# Voice.net
KiCad netlist of a schematic drawn in Altium Designer
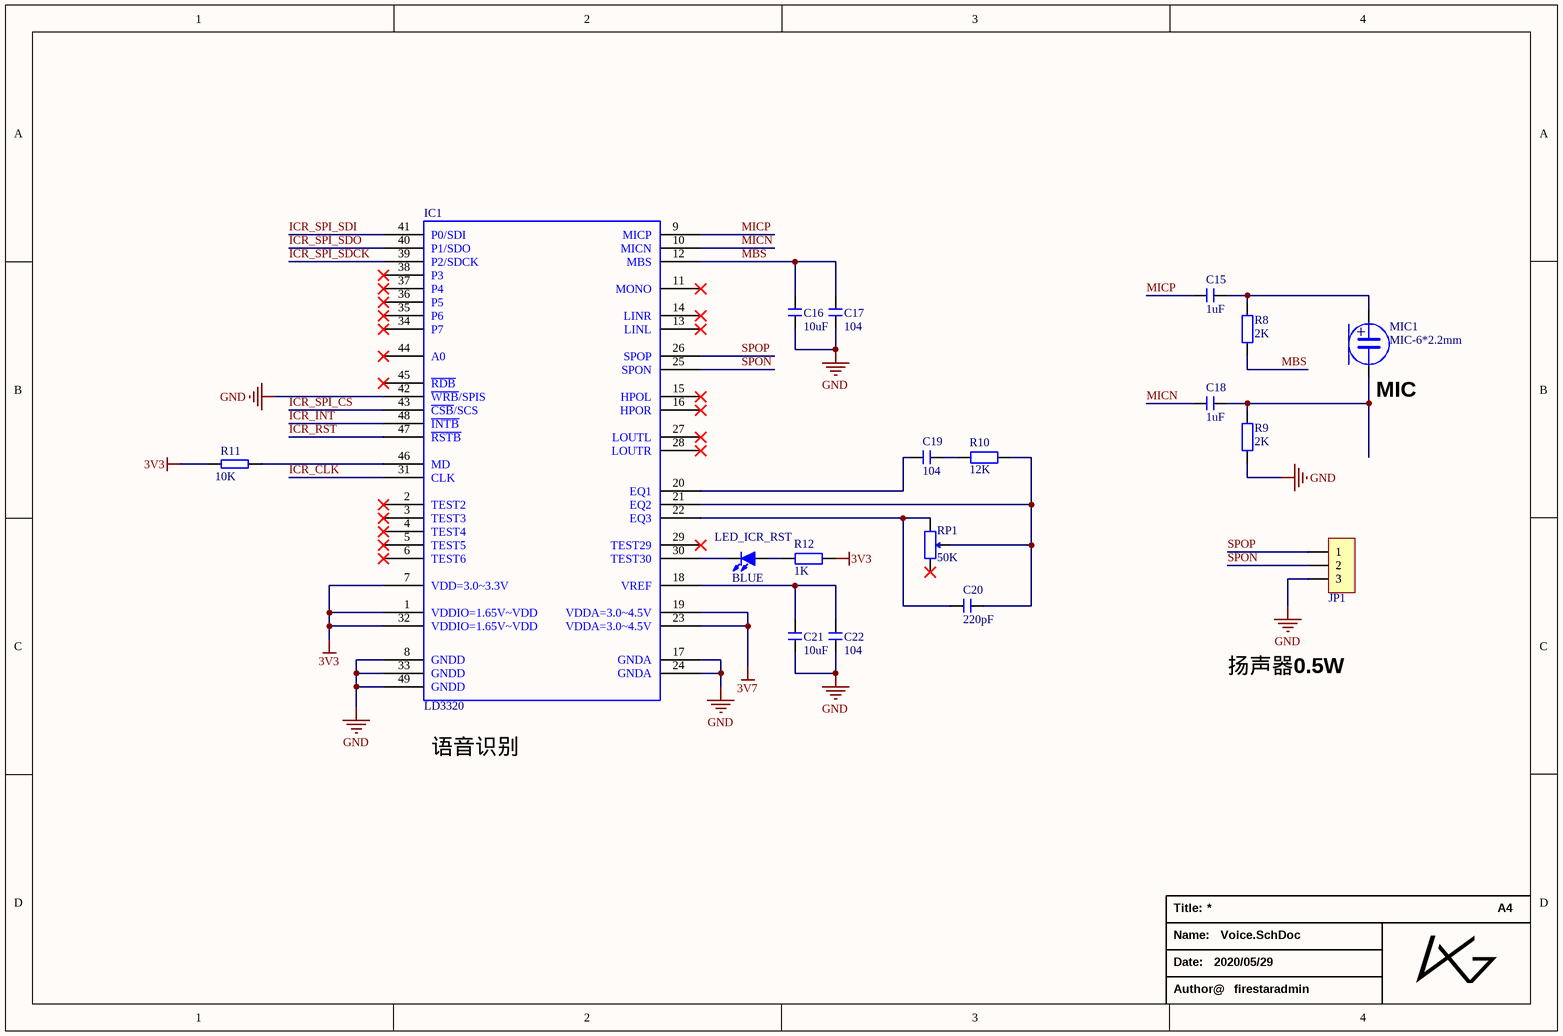
[diagram p0: Voice.SchDoc]

(export (version "E")
  (design (tool "Eeschema 10.0.6"))
  (components
    (comp (ref "C15")
      (value "1uF")
      (footprint "C 0603_M")
      (description "无极性贴片电容")
      (fields (field (name "版权归属") "源创客"))
      (libsource (lib "3.1   - 电阻-电容-电感") (part "C"))
    )
    (comp (ref "C16")
      (value "10uF")
      (footprint "C 0805_M")
      (description "无极性贴片电容")
      (fields (field (name "版权归属") "源创客"))
      (libsource (lib "3.1   - 电阻-电容-电感") (part "C"))
    )
    (comp (ref "C17")
      (value "104")
      (footprint "C 0603_M")
      (description "无极性贴片电容")
      (fields (field (name "版权归属") "源创客"))
      (libsource (lib "3.1   - 电阻-电容-电感") (part "C"))
    )
    (comp (ref "C18")
      (value "1uF")
      (footprint "C 0603_M")
      (description "无极性贴片电容")
      (fields (field (name "版权归属") "源创客"))
      (libsource (lib "3.1   - 电阻-电容-电感") (part "C"))
    )
    (comp (ref "C19")
      (value "104")
      (footprint "C 0603_M")
      (description "无极性贴片电容")
      (fields (field (name "版权归属") "源创客"))
      (libsource (lib "3.1   - 电阻-电容-电感") (part "C"))
    )
    (comp (ref "C20")
      (value "220pF")
      (footprint "C 0603_M")
      (description "无极性贴片电容")
      (fields (field (name "版权归属") "源创客"))
      (libsource (lib "3.1   - 电阻-电容-电感") (part "C"))
    )
    (comp (ref "C21")
      (value "10uF")
      (footprint "C 0805_M")
      (description "无极性贴片电容")
      (fields (field (name "版权归属") "源创客"))
      (libsource (lib "3.1   - 电阻-电容-电感") (part "C"))
    )
    (comp (ref "C22")
      (value "104")
      (footprint "C 0603_M")
      (description "无极性贴片电容")
      (fields (field (name "版权归属") "源创客"))
      (libsource (lib "3.1   - 电阻-电容-电感") (part "C"))
    )
    (comp (ref "IC1")
      (value "LD3320")
      (footprint "QFN48 7X7_M")
      (libsource (lib "1.1   - IC芯片") (part "LD3320"))
    )
    (comp (ref "JP1")
      (value "HDR-1X3")
      (footprint "HDR2.54-LI-3P")
      (description "3P接插件")
      (fields (field (name "版权归属") "源创客"))
      (libsource (lib "4.5   - 接插件-脚距2.54") (part "Header 3"))
    )
    (comp (ref "LED_ICR_RST")
      (value "BLUE")
      (footprint "LED 0603B")
      (description "贴片LED")
      (fields (field (name "版权归属") "源创客"))
      (libsource (lib "9.1   - LED") (part "LED-SMD"))
    )
    (comp (ref "MIC1")
      (value "MIC-6*2.2mm")
      (footprint "MIC-6*2.2MM")
      (description "电容麦克风")
      (fields (field (name "版权归属") "源创客"))
      (libsource (lib "11.1 - 传感元件") (part "MIC1"))
    )
    (comp (ref "R8")
      (value "2K")
      (footprint "R 0805_M")
      (description "贴片电阻")
      (fields (field (name "版权归属") "源创客"))
      (libsource (lib "3.1   - 电阻-电容-电感") (part "R"))
    )
    (comp (ref "R9")
      (value "2K")
      (footprint "R 0805_M")
      (description "贴片电阻")
      (fields (field (name "版权归属") "源创客"))
      (libsource (lib "3.1   - 电阻-电容-电感") (part "R"))
    )
    (comp (ref "R10")
      (value "12K")
      (footprint "R 0805_M")
      (description "贴片电阻")
      (fields (field (name "版权归属") "源创客"))
      (libsource (lib "3.1   - 电阻-电容-电感") (part "R"))
    )
    (comp (ref "R11") (value "10K") (footprint "R 0603_M") (libsource (lib "ZIBO V2.0_Main") (part "R")))
    (comp (ref "R12")
      (value "1K")
      (footprint "R 0805_M")
      (description "贴片电阻")
      (fields (field (name "版权归属") "源创客"))
      (libsource (lib "3.1   - 电阻-电容-电感") (part "R"))
    )
    (comp (ref "RP1")
      (value "50K")
      (footprint "3306W")
      (description "插件单联电位器")
      (fields (field (name "版权归属") "源创客"))
      (libsource (lib "3.1   - 电阻-电容-电感") (part "RP-ID"))
    )
  )
  (nets
    (net (code "1") (name "/ICR_CLK") (class "Default")
      (node (ref "IC1") (pin "31") (pinfunction "CLK_31") (pintype "passive"))
    )
    (net (code "2") (name "/ICR_INT") (class "Default")
      (node (ref "IC1") (pin "48") (pinfunction "~{INTB}_48") (pintype "passive"))
    )
    (net (code "3") (name "/ICR_RST") (class "Default")
      (node (ref "IC1") (pin "47") (pinfunction "~{RSTB}_47") (pintype "passive"))
    )
    (net (code "4") (name "/ICR_SPI_CS") (class "Default")
      (node (ref "IC1") (pin "43") (pinfunction "~{CSB}/SCS_43") (pintype "passive"))
    )
    (net (code "5") (name "/ICR_SPI_SDCK") (class "Default")
      (node (ref "IC1") (pin "39") (pinfunction "P2/SDCK_39") (pintype "passive"))
    )
    (net (code "6") (name "/ICR_SPI_SDI") (class "Default")
      (node (ref "IC1") (pin "41") (pinfunction "P0/SDI_41") (pintype "passive"))
    )
    (net (code "7") (name "/ICR_SPI_SDO") (class "Default")
      (node (ref "IC1") (pin "40") (pinfunction "P1/SDO_40") (pintype "passive"))
    )
    (net (code "8") (name "/MBS") (class "Default")
      (node (ref "C16") (pin "2") (pinfunction "2_2") (pintype "passive"))
      (node (ref "C17") (pin "2") (pinfunction "2_2") (pintype "passive"))
      (node (ref "IC1") (pin "12") (pinfunction "MBS_12") (pintype "passive"))
      (node (ref "R8") (pin "1") (pinfunction "1_1") (pintype "passive"))
    )
    (net (code "9") (name "/MICN") (class "Default")
      (node (ref "C18") (pin "2") (pinfunction "2_2") (pintype "passive"))
      (node (ref "IC1") (pin "10") (pinfunction "MICN_10") (pintype "passive"))
    )
    (net (code "10") (name "/MICP") (class "Default")
      (node (ref "C15") (pin "2") (pinfunction "2_2") (pintype "passive"))
      (node (ref "IC1") (pin "9") (pinfunction "MICP_9") (pintype "passive"))
    )
    (net (code "11") (name "/SPON") (class "Default")
      (node (ref "IC1") (pin "25") (pinfunction "SPON_25") (pintype "passive"))
      (node (ref "JP1") (pin "2") (pinfunction "2_2") (pintype "passive"))
    )
    (net (code "12") (name "/SPOP") (class "Default")
      (node (ref "IC1") (pin "26") (pinfunction "SPOP_26") (pintype "passive"))
      (node (ref "JP1") (pin "1") (pinfunction "1_1") (pintype "passive"))
    )
    (net (code "13") (name "3V3") (class "Default")
      (node (ref "IC1") (pin "1") (pinfunction "VDDIO=1.65V~VDD_1") (pintype "passive"))
      (node (ref "IC1") (pin "32") (pinfunction "VDDIO=1.65V~VDD_32") (pintype "passive"))
      (node (ref "IC1") (pin "7") (pinfunction "VDD=3.0~3.3V_7") (pintype "passive"))
      (node (ref "R11") (pin "1") (pinfunction "1_1") (pintype "passive"))
      (node (ref "R12") (pin "2") (pinfunction "2_2") (pintype "passive"))
    )
    (net (code "14") (name "3V7") (class "Default")
      (node (ref "IC1") (pin "19") (pinfunction "VDDA=3.0~4.5V_19") (pintype "passive"))
      (node (ref "IC1") (pin "23") (pinfunction "VDDA=3.0~4.5V_23") (pintype "passive"))
    )
    (net (code "15") (name "GND") (class "Default")
      (node (ref "C16") (pin "1") (pinfunction "1_1") (pintype "passive"))
      (node (ref "C17") (pin "1") (pinfunction "1_1") (pintype "passive"))
      (node (ref "C21") (pin "1") (pinfunction "1_1") (pintype "passive"))
      (node (ref "C22") (pin "1") (pinfunction "1_1") (pintype "passive"))
      (node (ref "IC1") (pin "17") (pinfunction "GNDA_17") (pintype "passive"))
      (node (ref "IC1") (pin "24") (pinfunction "GNDA_24") (pintype "passive"))
      (node (ref "IC1") (pin "33") (pinfunction "GNDD_33") (pintype "passive"))
      (node (ref "IC1") (pin "42") (pinfunction "~{WRB}/SPIS_42") (pintype "passive"))
      (node (ref "IC1") (pin "49") (pinfunction "GNDD_49") (pintype "passive"))
      (node (ref "IC1") (pin "8") (pinfunction "GNDD_8") (pintype "passive"))
      (node (ref "JP1") (pin "3") (pinfunction "3_3") (pintype "passive"))
      (node (ref "R9") (pin "1") (pinfunction "1_1") (pintype "passive"))
    )
    (net (code "16") (name "Net-(C15-Pad1)") (class "Default")
      (node (ref "C15") (pin "1") (pinfunction "1_1") (pintype "passive"))
      (node (ref "MIC1") (pin "1") (pinfunction "1_1") (pintype "passive"))
      (node (ref "R8") (pin "2") (pinfunction "2_2") (pintype "passive"))
    )
    (net (code "17") (name "Net-(C18-Pad1)") (class "Default")
      (node (ref "C18") (pin "1") (pinfunction "1_1") (pintype "passive"))
      (node (ref "MIC1") (pin "2") (pinfunction "2_2") (pintype "passive"))
      (node (ref "R9") (pin "2") (pinfunction "2_2") (pintype "passive"))
    )
    (net (code "18") (name "Net-(C19-Pad1)") (class "Default")
      (node (ref "C19") (pin "1") (pinfunction "1_1") (pintype "passive"))
      (node (ref "R10") (pin "1") (pinfunction "1_1") (pintype "passive"))
    )
    (net (code "19") (name "Net-(IC1-EQ1)") (class "Default")
      (node (ref "C19") (pin "2") (pinfunction "2_2") (pintype "passive"))
      (node (ref "IC1") (pin "20") (pinfunction "EQ1_20") (pintype "passive"))
    )
    (net (code "20") (name "Net-(IC1-EQ2)") (class "Default")
      (node (ref "C20") (pin "1") (pinfunction "1_1") (pintype "passive"))
      (node (ref "IC1") (pin "21") (pinfunction "EQ2_21") (pintype "passive"))
      (node (ref "R10") (pin "2") (pinfunction "2_2") (pintype "passive"))
      (node (ref "RP1") (pin "2") (pinfunction "2_2") (pintype "passive"))
    )
    (net (code "21") (name "Net-(IC1-EQ3)") (class "Default")
      (node (ref "C20") (pin "2") (pinfunction "2_2") (pintype "passive"))
      (node (ref "IC1") (pin "22") (pinfunction "EQ3_22") (pintype "passive"))
      (node (ref "RP1") (pin "1") (pinfunction "1_1") (pintype "passive"))
    )
    (net (code "22") (name "Net-(IC1-MD)") (class "Default")
      (node (ref "IC1") (pin "46") (pinfunction "MD_46") (pintype "passive"))
      (node (ref "R11") (pin "2") (pinfunction "2_2") (pintype "passive"))
    )
    (net (code "23") (name "Net-(IC1-TEST30)") (class "Default")
      (node (ref "IC1") (pin "30") (pinfunction "TEST30_30") (pintype "passive"))
      (node (ref "LED_ICR_RST") (pin "2") (pinfunction "K_2") (pintype "passive"))
    )
    (net (code "24") (name "Net-(IC1-VREF)") (class "Default")
      (node (ref "C21") (pin "2") (pinfunction "2_2") (pintype "passive"))
      (node (ref "C22") (pin "2") (pinfunction "2_2") (pintype "passive"))
      (node (ref "IC1") (pin "18") (pinfunction "VREF_18") (pintype "passive"))
    )
    (net (code "25") (name "Net-(LED_ICR_RST-A)") (class "Default")
      (node (ref "LED_ICR_RST") (pin "1") (pinfunction "A_1") (pintype "passive"))
      (node (ref "R12") (pin "1") (pinfunction "1_1") (pintype "passive"))
    )
    (net (code "26") (name "unconnected-(IC1-A0-Pad44)") (class "Default")
      (node (ref "IC1") (pin "44") (pinfunction "A0_44") (pintype "passive+no_connect"))
    )
    (net (code "27") (name "unconnected-(IC1-HPOL-Pad15)") (class "Default")
      (node (ref "IC1") (pin "15") (pinfunction "HPOL_15") (pintype "passive+no_connect"))
    )
    (net (code "28") (name "unconnected-(IC1-HPOR-Pad16)") (class "Default")
      (node (ref "IC1") (pin "16") (pinfunction "HPOR_16") (pintype "passive+no_connect"))
    )
    (net (code "29") (name "unconnected-(IC1-LINL-Pad13)") (class "Default")
      (node (ref "IC1") (pin "13") (pinfunction "LINL_13") (pintype "passive+no_connect"))
    )
    (net (code "30") (name "unconnected-(IC1-LINR-Pad14)") (class "Default")
      (node (ref "IC1") (pin "14") (pinfunction "LINR_14") (pintype "passive+no_connect"))
    )
    (net (code "31") (name "unconnected-(IC1-LOUTL-Pad27)") (class "Default")
      (node (ref "IC1") (pin "27") (pinfunction "LOUTL_27") (pintype "passive+no_connect"))
    )
    (net (code "32") (name "unconnected-(IC1-LOUTR-Pad28)") (class "Default")
      (node (ref "IC1") (pin "28") (pinfunction "LOUTR_28") (pintype "passive+no_connect"))
    )
    (net (code "33") (name "unconnected-(IC1-MONO-Pad11)") (class "Default")
      (node (ref "IC1") (pin "11") (pinfunction "MONO_11") (pintype "passive+no_connect"))
    )
    (net (code "34") (name "unconnected-(IC1-P3-Pad38)") (class "Default")
      (node (ref "IC1") (pin "38") (pinfunction "P3_38") (pintype "passive+no_connect"))
    )
    (net (code "35") (name "unconnected-(IC1-P4-Pad37)") (class "Default")
      (node (ref "IC1") (pin "37") (pinfunction "P4_37") (pintype "passive+no_connect"))
    )
    (net (code "36") (name "unconnected-(IC1-P5-Pad36)") (class "Default")
      (node (ref "IC1") (pin "36") (pinfunction "P5_36") (pintype "passive+no_connect"))
    )
    (net (code "37") (name "unconnected-(IC1-P6-Pad35)") (class "Default")
      (node (ref "IC1") (pin "35") (pinfunction "P6_35") (pintype "passive+no_connect"))
    )
    (net (code "38") (name "unconnected-(IC1-P7-Pad34)") (class "Default")
      (node (ref "IC1") (pin "34") (pinfunction "P7_34") (pintype "passive+no_connect"))
    )
    (net (code "39") (name "unconnected-(IC1-TEST2-Pad2)") (class "Default")
      (node (ref "IC1") (pin "2") (pinfunction "TEST2_2") (pintype "passive+no_connect"))
    )
    (net (code "40") (name "unconnected-(IC1-TEST3-Pad3)") (class "Default")
      (node (ref "IC1") (pin "3") (pinfunction "TEST3_3") (pintype "passive+no_connect"))
    )
    (net (code "41") (name "unconnected-(IC1-TEST4-Pad4)") (class "Default")
      (node (ref "IC1") (pin "4") (pinfunction "TEST4_4") (pintype "passive+no_connect"))
    )
    (net (code "42") (name "unconnected-(IC1-TEST5-Pad5)") (class "Default")
      (node (ref "IC1") (pin "5") (pinfunction "TEST5_5") (pintype "passive+no_connect"))
    )
    (net (code "43") (name "unconnected-(IC1-TEST6-Pad6)") (class "Default")
      (node (ref "IC1") (pin "6") (pinfunction "TEST6_6") (pintype "passive+no_connect"))
    )
    (net (code "44") (name "unconnected-(IC1-TEST29-Pad29)") (class "Default")
      (node (ref "IC1") (pin "29") (pinfunction "TEST29_29") (pintype "passive+no_connect"))
    )
    (net (code "45") (name "unconnected-(IC1-~{RDB}-Pad45)") (class "Default")
      (node (ref "IC1") (pin "45") (pinfunction "~{RDB}_45") (pintype "passive+no_connect"))
    )
    (net (code "46") (name "unconnected-(RP1-Pad3)") (class "Default")
      (node (ref "RP1") (pin "3") (pinfunction "3_3") (pintype "passive+no_connect"))
    )
  )
)
